# HomeAutomation_relay.net
KiCad netlist of a schematic drawn in EAGLE
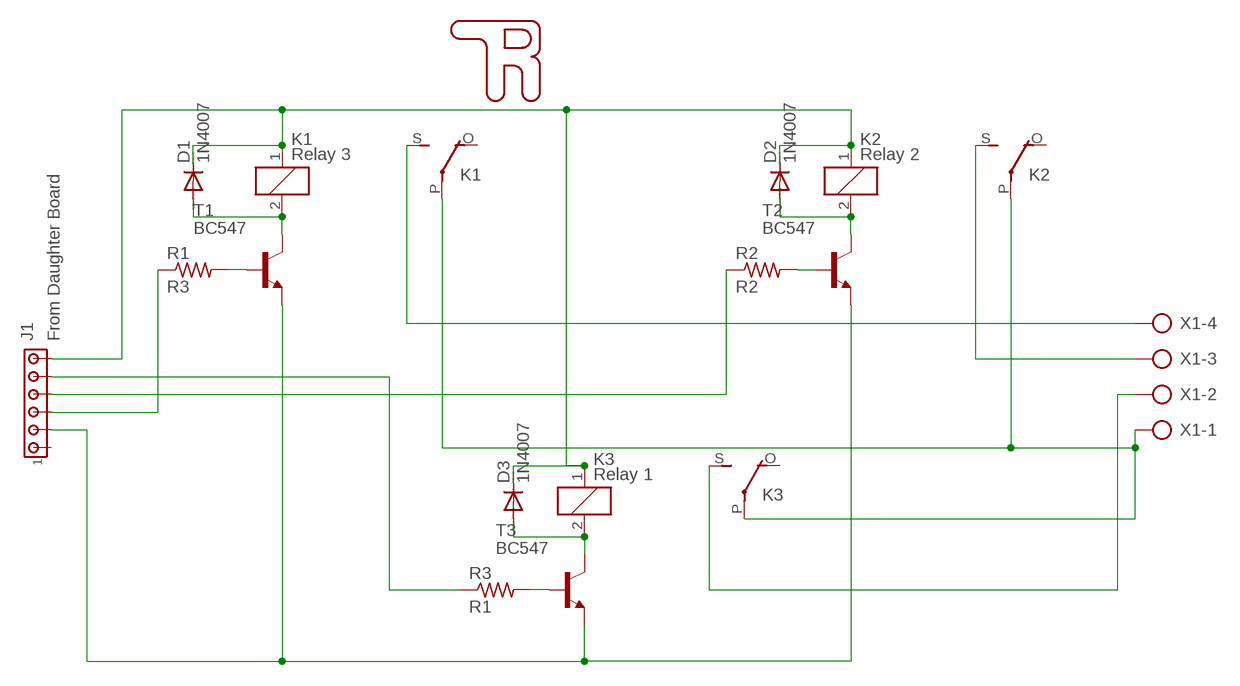
[diagram p0: schematic, sheet 1]

(export (version "E")
  (design (tool "Eeschema 10.0.6"))
  (components
    (comp (ref "D1")
      (value "1N4007")
      (footprint "eagle-import:DO41-10")
      (libsource (lib "eagle-import") (part "1N4004"))
    )
    (comp (ref "D2")
      (value "1N4007")
      (footprint "eagle-import:DO41-10")
      (libsource (lib "eagle-import") (part "1N4004"))
    )
    (comp (ref "D3")
      (value "1N4007")
      (footprint "eagle-import:DO41-10")
      (libsource (lib "eagle-import") (part "1N4004"))
    )
    (comp (ref "J1")
      (value "From Daughter Board")
      (footprint "eagle-import:10X06MTA")
      (libsource (lib "eagle-import") (part "MTA06-100"))
    )
    (comp (ref "K1")
      (value "Relay 3")
      (footprint "eagle-import:G5LE")
      (libsource (lib "eagle-import") (part "G5LE"))
    )
    (comp (ref "K2")
      (value "Relay 2")
      (footprint "eagle-import:G5LE")
      (libsource (lib "eagle-import") (part "G5LE"))
    )
    (comp (ref "K3")
      (value "Relay 1")
      (footprint "eagle-import:G5LE")
      (libsource (lib "eagle-import") (part "G5LE"))
    )
    (comp (ref "R1")
      (value "R3")
      (footprint "eagle-import:0204_7")
      (libsource (lib "eagle-import") (part "R-US_0204/7"))
    )
    (comp (ref "R2")
      (value "R2")
      (footprint "eagle-import:0204_7")
      (libsource (lib "eagle-import") (part "R-US_0204/7"))
    )
    (comp (ref "R3")
      (value "R1")
      (footprint "eagle-import:0204_7")
      (libsource (lib "eagle-import") (part "R-US_0204/7"))
    )
    (comp (ref "T1")
      (value "BC547")
      (footprint "eagle-import:TO92")
      (libsource (lib "eagle-import") (part "BC547"))
    )
    (comp (ref "T2")
      (value "BC547")
      (footprint "eagle-import:TO92")
      (libsource (lib "eagle-import") (part "BC547"))
    )
    (comp (ref "T3")
      (value "BC547")
      (footprint "eagle-import:TO92")
      (libsource (lib "eagle-import") (part "BC547"))
    )
    (comp (ref "U$1")
      (value "TRLOGO1")
      (footprint "eagle-import:TRLOGO_14")
      (libsource (lib "eagle-import") (part "TRLOGO1"))
    )
    (comp (ref "X1")
      (value "AK300/4")
      (footprint "eagle-import:AK300_4")
      (libsource (lib "eagle-import") (part "AK300/4"))
    )
  )
  (nets
    (net (code "1") (name "Net-(D1-PadC)") (class "Default")
      (node (ref "D1") (pin "C") (pinfunction "C_C") (pintype "passive"))
      (node (ref "D2") (pin "C") (pinfunction "C_C") (pintype "passive"))
      (node (ref "D3") (pin "C") (pinfunction "C_C") (pintype "passive"))
      (node (ref "J1") (pin "6") (pinfunction "6_6") (pintype "passive"))
      (node (ref "K1") (pin "1") (pinfunction "1_1") (pintype "passive"))
      (node (ref "K2") (pin "1") (pinfunction "1_1") (pintype "passive"))
      (node (ref "K3") (pin "1") (pinfunction "1_1") (pintype "passive"))
    )
    (net (code "2") (name "Net-(J1-Pad3)") (class "Default")
      (node (ref "J1") (pin "3") (pinfunction "3_3") (pintype "passive"))
      (node (ref "R1") (pin "1") (pinfunction "1_1") (pintype "passive"))
    )
    (net (code "3") (name "Net-(J1-Pad4)") (class "Default")
      (node (ref "J1") (pin "4") (pinfunction "4_4") (pintype "passive"))
      (node (ref "R2") (pin "1") (pinfunction "1_1") (pintype "passive"))
    )
    (net (code "4") (name "Net-(J1-Pad5)") (class "Default")
      (node (ref "J1") (pin "5") (pinfunction "5_5") (pintype "passive"))
      (node (ref "R3") (pin "1") (pinfunction "1_1") (pintype "passive"))
    )
    (net (code "5") (name "Net-(T1-B)") (class "Default")
      (node (ref "R1") (pin "2") (pinfunction "2_2") (pintype "passive"))
      (node (ref "T1") (pin "2") (pinfunction "B_2") (pintype "passive"))
    )
    (net (code "6") (name "Net-(T1-C)") (class "Default")
      (node (ref "D1") (pin "A") (pinfunction "A_A") (pintype "passive"))
      (node (ref "K1") (pin "2") (pinfunction "2_2") (pintype "passive"))
      (node (ref "T1") (pin "3") (pinfunction "C_3") (pintype "passive"))
    )
    (net (code "7") (name "Net-(T1-E)") (class "Default")
      (node (ref "J1") (pin "2") (pinfunction "2_2") (pintype "passive"))
      (node (ref "T1") (pin "1") (pinfunction "E_1") (pintype "passive"))
      (node (ref "T2") (pin "1") (pinfunction "E_1") (pintype "passive"))
      (node (ref "T3") (pin "1") (pinfunction "E_1") (pintype "passive"))
    )
    (net (code "8") (name "Net-(T2-B)") (class "Default")
      (node (ref "R2") (pin "2") (pinfunction "2_2") (pintype "passive"))
      (node (ref "T2") (pin "2") (pinfunction "B_2") (pintype "passive"))
    )
    (net (code "9") (name "Net-(T2-C)") (class "Default")
      (node (ref "D2") (pin "A") (pinfunction "A_A") (pintype "passive"))
      (node (ref "K2") (pin "2") (pinfunction "2_2") (pintype "passive"))
      (node (ref "T2") (pin "3") (pinfunction "C_3") (pintype "passive"))
    )
    (net (code "10") (name "Net-(T3-B)") (class "Default")
      (node (ref "R3") (pin "2") (pinfunction "2_2") (pintype "passive"))
      (node (ref "T3") (pin "2") (pinfunction "B_2") (pintype "passive"))
    )
    (net (code "11") (name "Net-(T3-C)") (class "Default")
      (node (ref "D3") (pin "A") (pinfunction "A_A") (pintype "passive"))
      (node (ref "K3") (pin "2") (pinfunction "2_2") (pintype "passive"))
      (node (ref "T3") (pin "3") (pinfunction "C_3") (pintype "passive"))
    )
    (net (code "12") (name "Net-(X1A-KL)") (class "Default")
      (node (ref "K1") (pin "P") (pinfunction "P_P") (pintype "passive"))
      (node (ref "K2") (pin "P") (pinfunction "P_P") (pintype "passive"))
      (node (ref "K3") (pin "P") (pinfunction "P_P") (pintype "passive"))
      (node (ref "X1") (pin "1") (pinfunction "KL_1") (pintype "passive"))
    )
    (net (code "13") (name "Net-(X1B-KL)") (class "Default")
      (node (ref "K3") (pin "S") (pinfunction "S_S") (pintype "passive"))
      (node (ref "X1") (pin "2") (pinfunction "KL_2") (pintype "passive"))
    )
    (net (code "14") (name "Net-(X1C-KL)") (class "Default")
      (node (ref "K2") (pin "S") (pinfunction "S_S") (pintype "passive"))
      (node (ref "X1") (pin "3") (pinfunction "KL_3") (pintype "passive"))
    )
    (net (code "15") (name "Net-(X1D-KL)") (class "Default")
      (node (ref "K1") (pin "S") (pinfunction "S_S") (pintype "passive"))
      (node (ref "X1") (pin "4") (pinfunction "KL_4") (pintype "passive"))
    )
    (net (code "16") (name "unconnected-(J1-Pad1)") (class "Default")
      (node (ref "J1") (pin "1") (pinfunction "1_1") (pintype "passive"))
    )
    (net (code "17") (name "unconnected-(K1-PadO)") (class "Default")
      (node (ref "K1") (pin "O") (pinfunction "O_O") (pintype "passive"))
    )
    (net (code "18") (name "unconnected-(K2-PadO)") (class "Default")
      (node (ref "K2") (pin "O") (pinfunction "O_O") (pintype "passive"))
    )
    (net (code "19") (name "unconnected-(K3-PadO)") (class "Default")
      (node (ref "K3") (pin "O") (pinfunction "O_O") (pintype "passive"))
    )
  )
)
